# ScopeVideo.net
KiCad netlist of a schematic drawn in Altium Designer
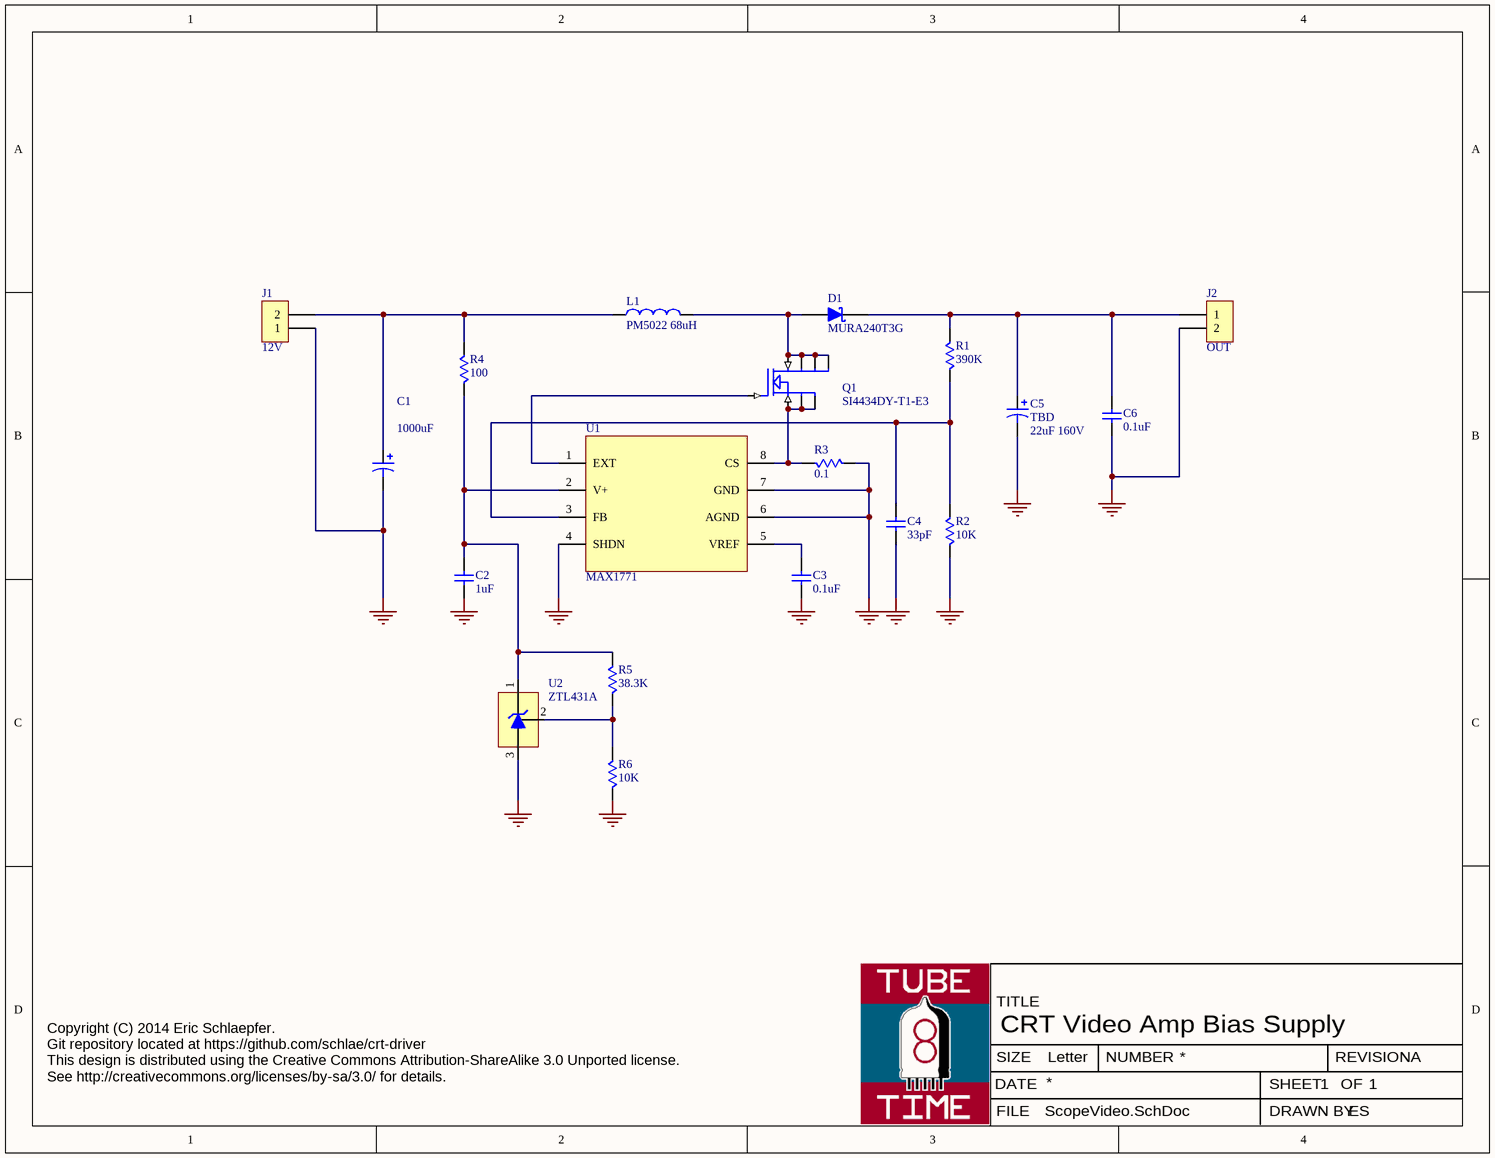
[diagram p0: ScopeVideo.SchDoc]

(export (version "E")
  (design (tool "Eeschema 10.0.6"))
  (components
    (comp (ref "C1")
      (value "1000uF")
      (footprint "CAP_R200x400")
      (description "Polarized Capacitor")
      (fields (field (name "MANUFPART") "UVR1E102MPD") (field (name "Comment") "Cap Pol2"))
      (libsource (lib "ClikCommon") (part "CapP"))
    )
    (comp (ref "C2")
      (value "1uF")
      (footprint "G_0805[2012]")
      (description "Capacitor")
      (fields (field (name "MANUFPART") "C2012X7R1E105K125AB") (field (name "Comment") "Cap"))
      (libsource (lib "ClikCommon") (part "Cap"))
    )
    (comp (ref "C3")
      (value "0.1uF")
      (footprint "G_0805[2012]")
      (description "Capacitor")
      (fields (field (name "Comment") "Cap"))
      (libsource (lib "ClikCommon") (part "Cap"))
    )
    (comp (ref "C4")
      (value "33pF")
      (footprint "G_0805[2012]")
      (description "Capacitor")
      (fields (field (name "Comment") "Cap"))
      (libsource (lib "ClikCommon") (part "Cap"))
    )
    (comp (ref "C5")
      (value "TBD")
      (footprint "CAP_R200x400")
      (description "Polarized Capacitor")
      (fields (field (name "ALTIUM_VALUE") "22uF 160V") (field (name "MANUFPART") "EEU-EE2C220"))
      (libsource (lib "ClikCommon") (part "CapP"))
    )
    (comp (ref "C6")
      (value "0.1uF")
      (footprint "G_1206[3216]")
      (description "Capacitor")
      (fields (field (name "MANUFPART") "C3216X7R2E104K160AA") (field (name "Comment") "Cap"))
      (libsource (lib "ClikCommon") (part "Cap"))
    )
    (comp (ref "D1")
      (value "MURA240T3G")
      (footprint "G_SMB")
      (description "Schottky Diode")
      (libsource (lib "ClikCommon") (part "D Schottky"))
    )
    (comp (ref "J1")
      (value "12V")
      (footprint "HDR2S156")
      (description "Connector, 2 pin")
      (libsource (lib "ClikConnectors") (part "CON2"))
    )
    (comp (ref "J2")
      (value "OUT")
      (footprint "HDR3SM1")
      (description "Connector, 2 pin")
      (libsource (lib "") (part "CON2_1"))
    )
    (comp (ref "L1")
      (value "PM5022 68uH")
      (footprint "IND1")
      (description "Inductor")
      (fields (field (name "MANUFPART") "PM5022-680M-RC"))
      (libsource (lib "*") (part "INDUCTOR"))
    )
    (comp (ref "Q1")
      (value "SI4434DY-T1-E3")
      (footprint "G_SO8")
      (description "N-channel MOSFET (8-SOIC)")
      (libsource (lib "*") (part "MOSFET N SO8"))
    )
    (comp (ref "R1")
      (value "390K")
      (footprint "G_0805[2012]")
      (description "Resistor")
      (fields (field (name "MANUFPART") "CRCW0805390KFKEA") (field (name "Comment") "Res1"))
      (libsource (lib "ClikCommon") (part "Res"))
    )
    (comp (ref "R2")
      (value "10K")
      (footprint "G_0805[2012]")
      (description "Resistor")
      (fields (field (name "MANUFPART") "CRCW080510K0FKEB") (field (name "Comment") "Res1"))
      (libsource (lib "ClikCommon") (part "Res"))
    )
    (comp (ref "R3")
      (value "0.1")
      (footprint "G_1210[3225]")
      (description "Resistor")
      (fields (field (name "MANUFPART") "73L5R10J") (field (name "Comment") "Res1"))
      (libsource (lib "ClikCommon") (part "Res"))
    )
    (comp (ref "R4")
      (value "100")
      (footprint "G_0805[2012]")
      (description "Resistor")
      (fields (field (name "MANUFPART") "CRCW0805100RFKEA") (field (name "Comment") "Res1"))
      (libsource (lib "ClikCommon") (part "Res"))
    )
    (comp (ref "R5")
      (value "38.3K")
      (footprint "G_0805[2012]")
      (description "Resistor")
      (fields (field (name "MANUFPART") "CRCW080538K3FKEA") (field (name "Comment") "Res1"))
      (libsource (lib "ClikCommon") (part "Res"))
    )
    (comp (ref "R6")
      (value "10K")
      (footprint "G_0805[2012]")
      (description "Resistor")
      (fields (field (name "MANUFPART") "CRCW080510K0FKEB") (field (name "Comment") "Res1"))
      (libsource (lib "ClikCommon") (part "Res"))
    )
    (comp (ref "U1")
      (value "MAX1771")
      (footprint "G_SO8")
      (description "MAX1771 Boost Converter")
      (fields (field (name "MANUFPART") "MAX1771CSA+"))
      (libsource (lib "*") (part "MAX1771"))
    )
    (comp (ref "U2")
      (value "ZTL431A")
      (footprint "G_SOT23")
      (description "Adjustable Shunt Reg")
      (fields (field (name "MANUFPART") "ZTL431AFFTA"))
      (libsource (lib "ClikIC") (part "TL431"))
    )
  )
  (nets
    (net (code "1") (name "GND") (class "Default")
      (node (ref "C1") (pin "2") (pinfunction "2_2") (pintype "passive"))
      (node (ref "C2") (pin "1") (pinfunction "1_1") (pintype "passive"))
      (node (ref "C3") (pin "1") (pinfunction "1_1") (pintype "passive"))
      (node (ref "C4") (pin "1") (pinfunction "1_1") (pintype "passive"))
      (node (ref "C5") (pin "2") (pinfunction "2_2") (pintype "passive"))
      (node (ref "C6") (pin "1") (pinfunction "1_1") (pintype "passive"))
      (node (ref "J1") (pin "1") (pinfunction "1_1") (pintype "passive"))
      (node (ref "J2") (pin "2") (pinfunction "2_2") (pintype "passive"))
      (node (ref "R2") (pin "2") (pinfunction "2_2") (pintype "passive"))
      (node (ref "R3") (pin "2") (pinfunction "2_2") (pintype "passive"))
      (node (ref "R6") (pin "2") (pinfunction "2_2") (pintype "passive"))
      (node (ref "U1") (pin "4") (pinfunction "SHDN_4") (pintype "passive"))
      (node (ref "U1") (pin "6") (pinfunction "AGND_6") (pintype "power_in"))
      (node (ref "U1") (pin "7") (pinfunction "GND_7") (pintype "power_in"))
      (node (ref "U2") (pin "3") (pinfunction "A_3") (pintype "passive"))
    )
    (net (code "2") (name "Net-(C1-Pad1)") (class "Default")
      (node (ref "C1") (pin "1") (pinfunction "1_1") (pintype "passive"))
      (node (ref "J1") (pin "2") (pinfunction "2_2") (pintype "passive"))
      (node (ref "L1") (pin "1") (pinfunction "1_1") (pintype "passive"))
      (node (ref "R4") (pin "1") (pinfunction "1_1") (pintype "passive"))
    )
    (net (code "3") (name "Net-(C5-Pad1)") (class "Default")
      (node (ref "C5") (pin "1") (pinfunction "1_1") (pintype "passive"))
      (node (ref "C6") (pin "2") (pinfunction "2_2") (pintype "passive"))
      (node (ref "D1") (pin "K") (pinfunction "K_K") (pintype "passive"))
      (node (ref "J2") (pin "1") (pinfunction "1_1") (pintype "passive"))
      (node (ref "R1") (pin "1") (pinfunction "1_1") (pintype "passive"))
    )
    (net (code "4") (name "Net-(D1-PadA)") (class "Default")
      (node (ref "D1") (pin "A") (pinfunction "A_A") (pintype "passive"))
      (node (ref "L1") (pin "2") (pinfunction "2_2") (pintype "passive"))
      (node (ref "Q1") (pin "5") (pinfunction "D_5") (pintype "input"))
      (node (ref "Q1") (pin "6") (pinfunction "D_6") (pintype "passive"))
      (node (ref "Q1") (pin "7") (pinfunction "D_7") (pintype "passive"))
      (node (ref "Q1") (pin "8") (pinfunction "D_8") (pintype "passive"))
    )
    (net (code "5") (name "Net-(Q1-G)") (class "Default")
      (node (ref "Q1") (pin "4") (pinfunction "G_4") (pintype "input"))
      (node (ref "U1") (pin "1") (pinfunction "EXT_1") (pintype "passive"))
    )
    (net (code "6") (name "Net-(U1-CS)") (class "Default")
      (node (ref "Q1") (pin "1") (pinfunction "S_1") (pintype "input"))
      (node (ref "Q1") (pin "2") (pinfunction "S_2") (pintype "passive"))
      (node (ref "Q1") (pin "3") (pinfunction "S_3") (pintype "passive"))
      (node (ref "R3") (pin "1") (pinfunction "1_1") (pintype "passive"))
      (node (ref "U1") (pin "8") (pinfunction "CS_8") (pintype "passive"))
    )
    (net (code "7") (name "Net-(U1-FB)") (class "Default")
      (node (ref "C4") (pin "2") (pinfunction "2_2") (pintype "passive"))
      (node (ref "R1") (pin "2") (pinfunction "2_2") (pintype "passive"))
      (node (ref "R2") (pin "1") (pinfunction "1_1") (pintype "passive"))
      (node (ref "U1") (pin "3") (pinfunction "FB_3") (pintype "passive"))
    )
    (net (code "8") (name "Net-(U1-V+)") (class "Default")
      (node (ref "C2") (pin "2") (pinfunction "2_2") (pintype "passive"))
      (node (ref "R4") (pin "2") (pinfunction "2_2") (pintype "passive"))
      (node (ref "R5") (pin "1") (pinfunction "1_1") (pintype "passive"))
      (node (ref "U1") (pin "2") (pinfunction "V+_2") (pintype "power_in"))
      (node (ref "U2") (pin "1") (pinfunction "C_1") (pintype "passive"))
    )
    (net (code "9") (name "Net-(U1-VREF)") (class "Default")
      (node (ref "C3") (pin "2") (pinfunction "2_2") (pintype "passive"))
      (node (ref "U1") (pin "5") (pinfunction "VREF_5") (pintype "passive"))
    )
    (net (code "10") (name "Net-(U2-REF)") (class "Default")
      (node (ref "R5") (pin "2") (pinfunction "2_2") (pintype "passive"))
      (node (ref "R6") (pin "1") (pinfunction "1_1") (pintype "passive"))
      (node (ref "U2") (pin "2") (pinfunction "REF_2") (pintype "passive"))
    )
  )
)
